# USB_CPLD.net
KiCad netlist of a schematic drawn in Altium Designer
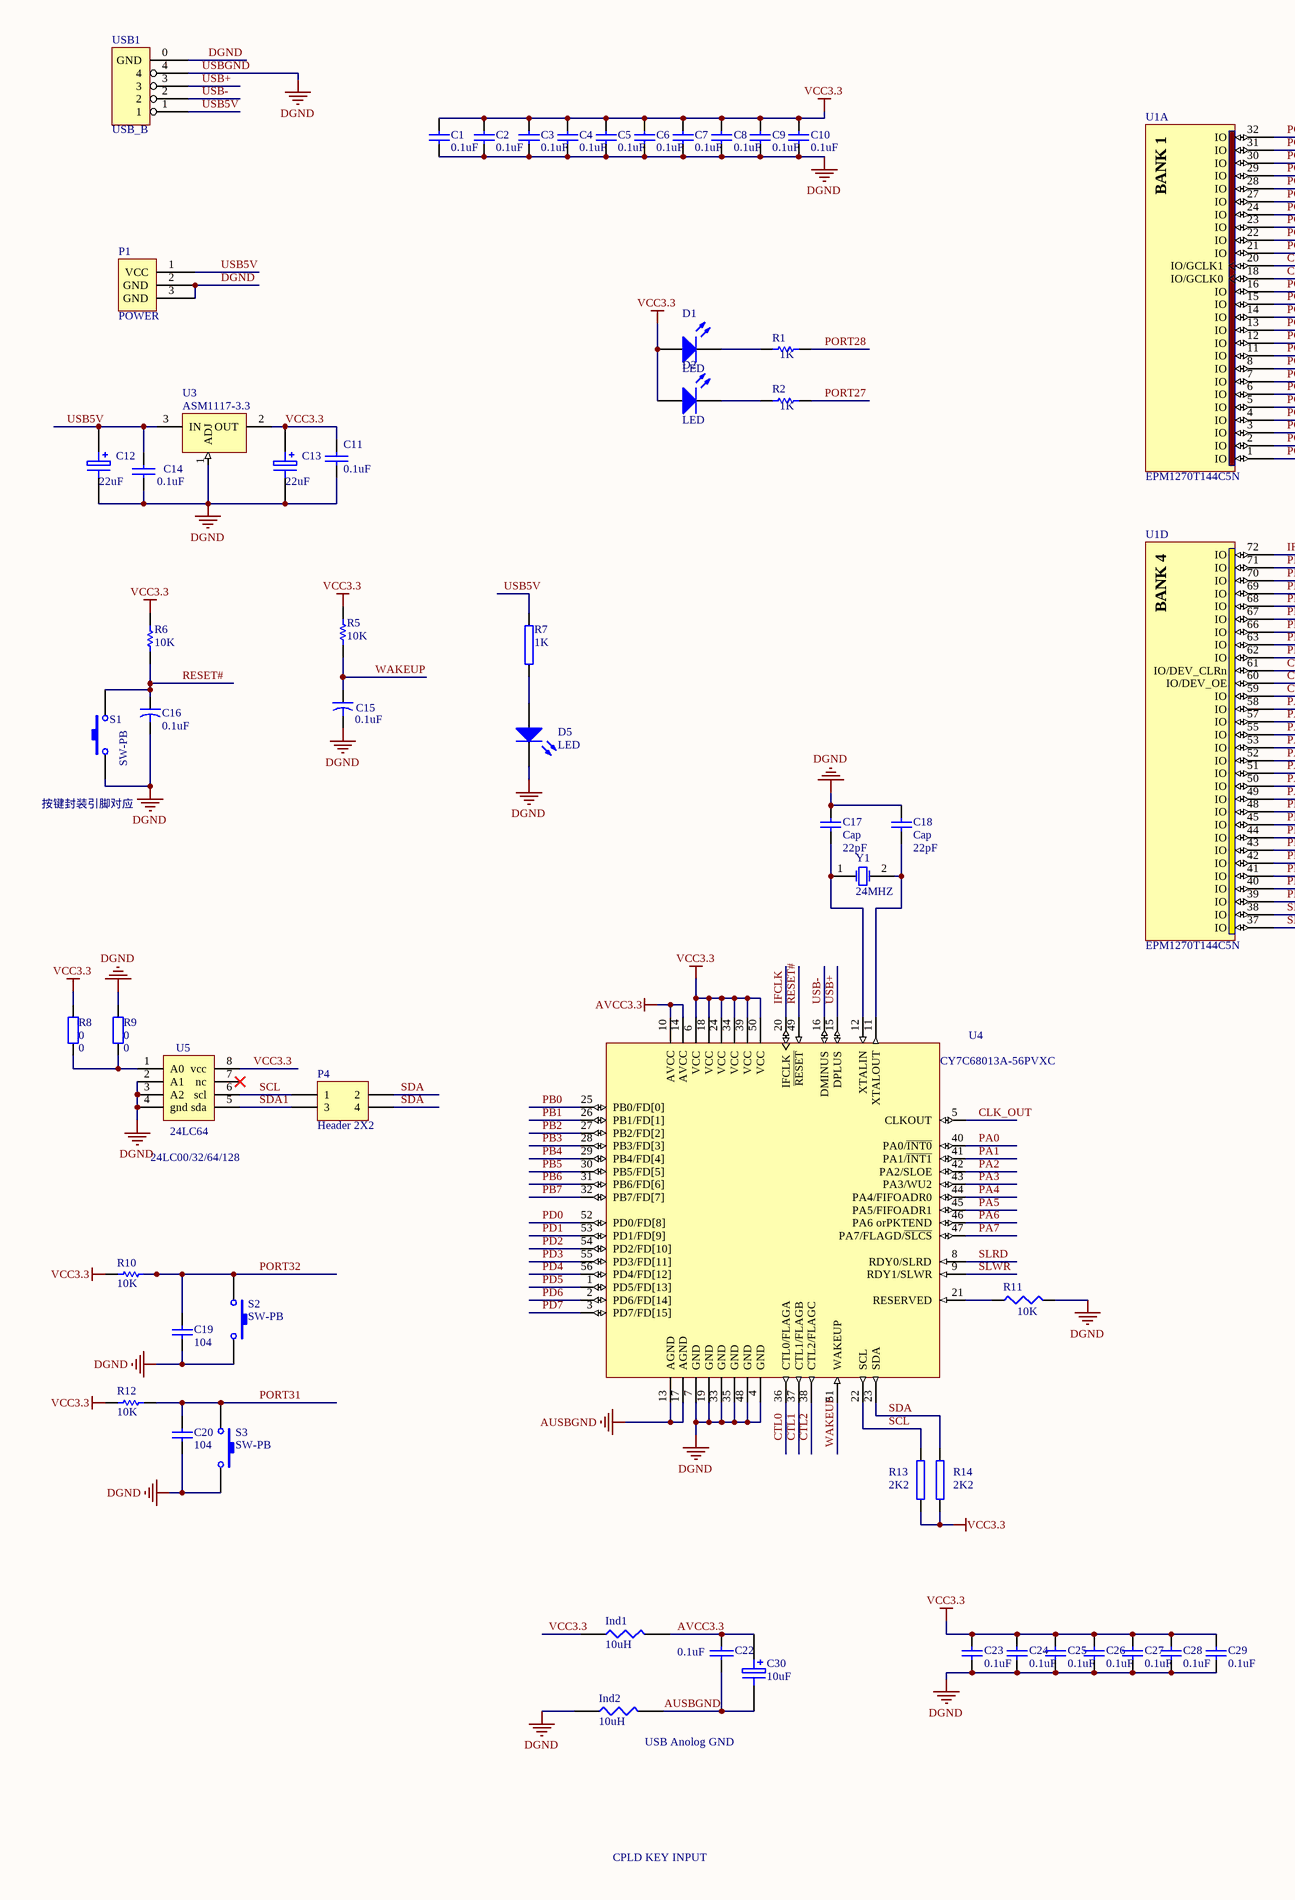
[diagram p0: USB_CPLD.SchDoc, left]
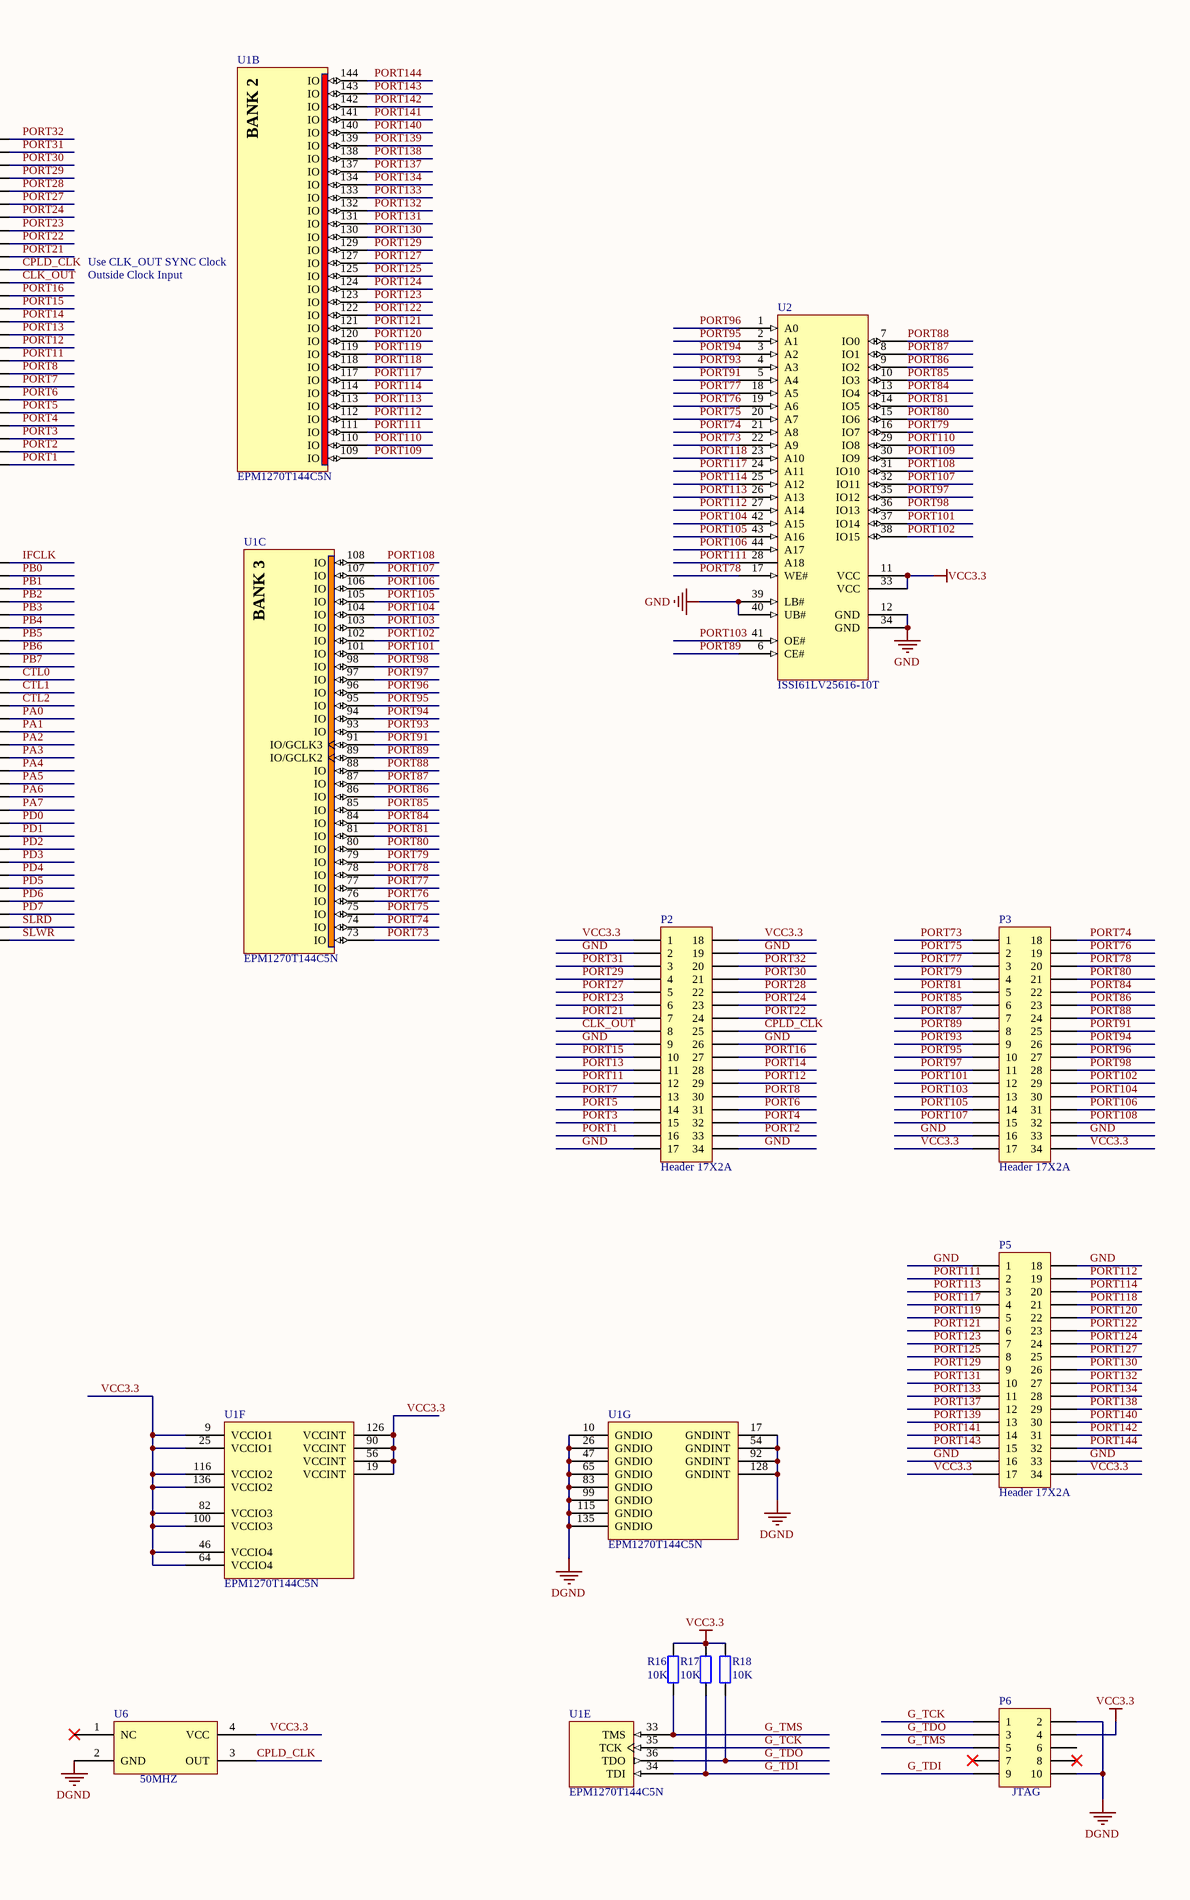
[diagram p1: USB_CPLD.SchDoc, right]

(export (version "E")
  (design (tool "Eeschema 10.0.6"))
  (components
    (comp (ref "C1")
      (value "0.1uF")
      (footprint "1608[0603]")
      (description "Capacitor (Semiconductor SIM Model)")
      (fields (field (name "PUBLISHER") "Altium Limited"))
      (libsource (lib "Miscellaneous Devices") (part "Cap Semi"))
    )
    (comp (ref "C2")
      (value "0.1uF")
      (footprint "1608[0603]")
      (description "Capacitor (Semiconductor SIM Model)")
      (fields (field (name "PUBLISHER") "Altium Limited"))
      (libsource (lib "Miscellaneous Devices") (part "Cap Semi"))
    )
    (comp (ref "C3")
      (value "0.1uF")
      (footprint "1608[0603]")
      (description "Capacitor (Semiconductor SIM Model)")
      (fields (field (name "Comment") "Cap Semi") (field (name "PUBLISHER") "Altium Limited"))
      (libsource (lib "Miscellaneous Devices") (part "Cap Semi"))
    )
    (comp (ref "C4")
      (value "0.1uF")
      (footprint "1608[0603]")
      (description "Capacitor (Semiconductor SIM Model)")
      (fields (field (name "Comment") "Cap Semi") (field (name "PUBLISHER") "Altium Limited"))
      (libsource (lib "Miscellaneous Devices") (part "Cap Semi"))
    )
    (comp (ref "C5")
      (value "0.1uF")
      (footprint "1608[0603]")
      (description "Capacitor (Semiconductor SIM Model)")
      (fields (field (name "Comment") "Cap Semi") (field (name "PUBLISHER") "Altium Limited"))
      (libsource (lib "Miscellaneous Devices") (part "Cap Semi"))
    )
    (comp (ref "C6")
      (value "0.1uF")
      (footprint "1608[0603]")
      (description "Capacitor (Semiconductor SIM Model)")
      (fields (field (name "Comment") "Cap Semi") (field (name "PUBLISHER") "Altium Limited"))
      (libsource (lib "Miscellaneous Devices") (part "Cap Semi"))
    )
    (comp (ref "C7")
      (value "0.1uF")
      (footprint "1608[0603]")
      (description "Capacitor (Semiconductor SIM Model)")
      (fields (field (name "Comment") "Cap Semi") (field (name "PUBLISHER") "Altium Limited"))
      (libsource (lib "Miscellaneous Devices") (part "Cap Semi"))
    )
    (comp (ref "C8")
      (value "0.1uF")
      (footprint "1608[0603]")
      (description "Capacitor (Semiconductor SIM Model)")
      (fields (field (name "Comment") "Cap Semi") (field (name "PUBLISHER") "Altium Limited"))
      (libsource (lib "Miscellaneous Devices") (part "Cap Semi"))
    )
    (comp (ref "C9")
      (value "0.1uF")
      (footprint "1608[0603]")
      (description "Capacitor (Semiconductor SIM Model)")
      (fields (field (name "Comment") "Cap Semi") (field (name "PUBLISHER") "Altium Limited"))
      (libsource (lib "Miscellaneous Devices") (part "Cap Semi"))
    )
    (comp (ref "C10")
      (value "0.1uF")
      (footprint "1608[0603]")
      (description "Capacitor (Semiconductor SIM Model)")
      (fields (field (name "Comment") "Cap Semi") (field (name "PUBLISHER") "Altium Limited"))
      (libsource (lib "Miscellaneous Devices") (part "Cap Semi"))
    )
    (comp (ref "C11")
      (value "0.1uF")
      (footprint "1608[0603]")
      (description "Capacitor")
      (libsource (lib "*") (part "CAP"))
    )
    (comp (ref "C12")
      (value "22uF")
      (footprint "3528")
      (description "Electrolytic Capacitor")
      (libsource (lib "*") (part "ELECTRO1"))
    )
    (comp (ref "C13")
      (value "22uF")
      (footprint "3528")
      (description "Electrolytic Capacitor")
      (libsource (lib "*") (part "ELECTRO1"))
    )
    (comp (ref "C14")
      (value "0.1uF")
      (footprint "1608[0603]")
      (description "Capacitor")
      (libsource (lib "*") (part "CAP"))
    )
    (comp (ref "C15")
      (value "0.1uF")
      (footprint "1206")
      (description "Capacitor")
      (fields (field (name "PUBLISHER") "Altium Limited"))
      (libsource (lib "*") (part "Cap2"))
    )
    (comp (ref "C16")
      (value "0.1uF")
      (footprint "1206")
      (description "Capacitor")
      (fields (field (name "PUBLISHER") "Altium Limited"))
      (libsource (lib "*") (part "Cap2"))
    )
    (comp (ref "C17")
      (value "Cap")
      (footprint "1608[0603]")
      (description "Capacitor")
      (fields (field (name "ALTIUM_VALUE") "22pF") (field (name "PUBLISHER") "Altium Limited"))
      (libsource (lib "*") (part "Cap"))
    )
    (comp (ref "C18")
      (value "Cap")
      (footprint "1608[0603]")
      (description "Capacitor")
      (fields (field (name "ALTIUM_VALUE") "22pF") (field (name "PUBLISHER") "Altium Limited"))
      (libsource (lib "*") (part "Cap"))
    )
    (comp (ref "C19")
      (value "104")
      (footprint "1608[0603]")
      (description "Capacitor (Semiconductor SIM Model)")
      (fields (field (name "PUBLISHER") "Altium Limited"))
      (libsource (lib "Miscellaneous Devices") (part "Cap Semi"))
    )
    (comp (ref "C20")
      (value "104")
      (footprint "1608[0603]")
      (description "Capacitor (Semiconductor SIM Model)")
      (fields (field (name "PUBLISHER") "Altium Limited"))
      (libsource (lib "Miscellaneous Devices") (part "Cap Semi"))
    )
    (comp (ref "C22")
      (value "0.1uF")
      (footprint "1608[0603]")
      (description "Capacitor")
      (libsource (lib "*") (part "CAP"))
    )
    (comp (ref "C23")
      (value "0.1uF")
      (footprint "1608[0603]")
      (description "Capacitor (Semiconductor SIM Model)")
      (fields (field (name "Comment") "Cap Semi") (field (name "PUBLISHER") "Altium Limited"))
      (libsource (lib "Miscellaneous Devices") (part "Cap Semi"))
    )
    (comp (ref "C24")
      (value "0.1uF")
      (footprint "1608[0603]")
      (description "Capacitor (Semiconductor SIM Model)")
      (fields (field (name "Comment") "Cap Semi") (field (name "PUBLISHER") "Altium Limited"))
      (libsource (lib "Miscellaneous Devices") (part "Cap Semi"))
    )
    (comp (ref "C25")
      (value "0.1uF")
      (footprint "1608[0603]")
      (description "Capacitor (Semiconductor SIM Model)")
      (fields (field (name "Comment") "Cap Semi") (field (name "PUBLISHER") "Altium Limited"))
      (libsource (lib "Miscellaneous Devices") (part "Cap Semi"))
    )
    (comp (ref "C26")
      (value "0.1uF")
      (footprint "1608[0603]")
      (description "Capacitor (Semiconductor SIM Model)")
      (fields (field (name "Comment") "Cap Semi") (field (name "PUBLISHER") "Altium Limited"))
      (libsource (lib "Miscellaneous Devices") (part "Cap Semi"))
    )
    (comp (ref "C27")
      (value "0.1uF")
      (footprint "1608[0603]")
      (description "Capacitor (Semiconductor SIM Model)")
      (fields (field (name "Comment") "Cap Semi") (field (name "PUBLISHER") "Altium Limited"))
      (libsource (lib "Miscellaneous Devices") (part "Cap Semi"))
    )
    (comp (ref "C28")
      (value "0.1uF")
      (footprint "1608[0603]")
      (description "Capacitor (Semiconductor SIM Model)")
      (fields (field (name "Comment") "Cap Semi") (field (name "PUBLISHER") "Altium Limited"))
      (libsource (lib "Miscellaneous Devices") (part "Cap Semi"))
    )
    (comp (ref "C29")
      (value "0.1uF")
      (footprint "1608[0603]")
      (description "Capacitor (Semiconductor SIM Model)")
      (fields (field (name "Comment") "Cap Semi") (field (name "PUBLISHER") "Altium Limited"))
      (libsource (lib "Miscellaneous Devices") (part "Cap Semi"))
    )
    (comp (ref "C30")
      (value "10uF")
      (footprint "1206")
      (description "Electrolytic Capacitor")
      (libsource (lib "*") (part "ELECTRO1"))
    )
    (comp (ref "D1")
      (value "LED")
      (footprint "LED-3")
      (description "Typical BLUE SiC LED")
      (fields (field (name "PUBLISHER") "Altium Limited"))
      (libsource (lib "*") (part "LED3"))
    )
    (comp (ref "D2")
      (value "LED")
      (footprint "LED-3")
      (description "Typical BLUE SiC LED")
      (fields (field (name "PUBLISHER") "Altium Limited"))
      (libsource (lib "*") (part "LED3"))
    )
    (comp (ref "D5")
      (value "LED")
      (footprint "LED-3")
      (description "Typical BLUE SiC LED")
      (fields (field (name "PUBLISHER") "Altium Limited"))
      (libsource (lib "*") (part "LED3"))
    )
    (comp (ref "Ind1") (value "10uH") (footprint "0805") (libsource (lib "*") (part "RES1")))
    (comp (ref "Ind2") (value "10uH") (footprint "0805") (libsource (lib "*") (part "RES1")))
    (comp (ref "P1") (value "POWER") (footprint "POWER_BIG") (libsource (lib "EP2C5T114核心板一") (part "POWER")))
    (comp (ref "P2")
      (value "Header 17X2A")
      (footprint "HDR2X17_CEN")
      (description "Header, 17-Pin, Dual row")
      (fields (field (name "PUBLISHER") "Altium Limited"))
      (libsource (lib "Miscellaneous Connectors") (part "Header 17X2A"))
    )
    (comp (ref "P3")
      (value "Header 17X2A")
      (footprint "HDR2X17_CEN")
      (description "Header, 17-Pin, Dual row")
      (fields (field (name "PUBLISHER") "Altium Limited"))
      (libsource (lib "Miscellaneous Connectors") (part "Header 17X2A"))
    )
    (comp (ref "P4")
      (value "Header 2X2")
      (footprint "HDR2X2")
      (description "Header, 2-Pin, Dual row")
      (fields (field (name "PUBLISHER") "Altium Limited"))
      (libsource (lib "Miscellaneous Connectors") (part "Header 2X2"))
    )
    (comp (ref "P5")
      (value "Header 17X2A")
      (footprint "HDR2X17_CEN")
      (description "Header, 17-Pin, Dual row")
      (fields (field (name "PUBLISHER") "Altium Limited"))
      (libsource (lib "Miscellaneous Connectors") (part "Header 17X2A"))
    )
    (comp (ref "P6")
      (value "JTAG")
      (footprint "HDR2X5")
      (description "Header, 5-Pin, Dual row")
      (fields (field (name "PUBLISHER") "Altium Limited"))
      (libsource (lib "*") (part "Header 5X2"))
    )
    (comp (ref "R1")
      (value "1K")
      (footprint "1608[0603]")
      (description "Resistor")
      (fields (field (name "Comment") "Res1") (field (name "PUBLISHER") "Altium Limited"))
      (libsource (lib "*") (part "Res1"))
    )
    (comp (ref "R2")
      (value "1K")
      (footprint "1608[0603]")
      (description "Resistor")
      (fields (field (name "Comment") "Res1") (field (name "PUBLISHER") "Altium Limited"))
      (libsource (lib "*") (part "Res1"))
    )
    (comp (ref "R5")
      (value "10K")
      (footprint "1608[0603]")
      (description "Resistor")
      (fields (field (name "PUBLISHER") "Altium Limited"))
      (libsource (lib "*") (part "Res1"))
    )
    (comp (ref "R6")
      (value "10K")
      (footprint "1608[0603]")
      (description "Resistor")
      (fields (field (name "PUBLISHER") "Altium Limited"))
      (libsource (lib "*") (part "Res1"))
    )
    (comp (ref "R7") (value "1K") (footprint "2012[0805]") (libsource (lib "*") (part "RES2")))
    (comp (ref "R8")
      (value "0")
      (footprint "1608[0603]")
      (description "Resistor")
      (fields (field (name "ALTIUM_VALUE") "0") (field (name "PUBLISHER") "Altium Limited"))
      (libsource (lib "Miscellaneous Devices") (part "Res2"))
    )
    (comp (ref "R9")
      (value "0")
      (footprint "1608[0603]")
      (description "Resistor")
      (fields (field (name "ALTIUM_VALUE") "0") (field (name "PUBLISHER") "Altium Limited"))
      (libsource (lib "Miscellaneous Devices") (part "Res2"))
    )
    (comp (ref "R10")
      (value "10K")
      (footprint "1608[0603]")
      (description "Resistor")
      (fields (field (name "PUBLISHER") "Altium Limited"))
      (libsource (lib "*") (part "Res1"))
    )
    (comp (ref "R11")
      (value "10K")
      (footprint "1608[0603]")
      (description "Resistor")
      (fields (field (name "Comment") "Res3") (field (name "PUBLISHER") "Altium Limited"))
      (libsource (lib "Miscellaneous Devices") (part "Res3"))
    )
    (comp (ref "R12")
      (value "10K")
      (footprint "1608[0603]")
      (description "Resistor")
      (fields (field (name "PUBLISHER") "Altium Limited"))
      (libsource (lib "*") (part "Res1"))
    )
    (comp (ref "R13") (value "2K2") (footprint "1608[0603]") (libsource (lib "*") (part "RES2")))
    (comp (ref "R14") (value "2K2") (footprint "1608[0603]") (libsource (lib "*") (part "RES2")))
    (comp (ref "R16")
      (value "10K")
      (footprint "1608[0603]")
      (description "Resistor")
      (fields (field (name "Comment") "300") (field (name "PUBLISHER") "Altium Limited"))
      (libsource (lib "*") (part "Res2"))
    )
    (comp (ref "R17")
      (value "10K")
      (footprint "1608[0603]")
      (description "Resistor")
      (fields (field (name "Comment") "300") (field (name "PUBLISHER") "Altium Limited"))
      (libsource (lib "*") (part "Res2"))
    )
    (comp (ref "R18")
      (value "10K")
      (footprint "1608[0603]")
      (description "Resistor")
      (fields (field (name "Comment") "300") (field (name "PUBLISHER") "Altium Limited"))
      (libsource (lib "*") (part "Res2"))
    )
    (comp (ref "S1")
      (value "SW-PB")
      (footprint "SW-6-6")
      (description "Switch")
      (fields (field (name "PUBLISHER") "Altium Limited"))
      (libsource (lib "*") (part "SW-PB"))
    )
    (comp (ref "S2")
      (value "SW-PB")
      (footprint "SW-6-6")
      (description "Switch")
      (fields (field (name "PUBLISHER") "Altium Limited"))
      (libsource (lib "*") (part "SW-PB"))
    )
    (comp (ref "S3")
      (value "SW-PB")
      (footprint "SW-6-6")
      (description "Switch")
      (fields (field (name "PUBLISHER") "Altium Limited"))
      (libsource (lib "*") (part "SW-PB"))
    )
    (comp (ref "U1")
      (value "EPM1270T144C5N")
      (footprint "TQFP144_N")
      (fields (field (name "PUBLISHER") "Altium Limited"))
      (libsource (lib "Altera MAX II") (part "EPM1270T144C5N"))
    )
    (comp (ref "U2")
      (value "ISSI61LV25616-10T")
      (footprint "TSOPII44")
      (description "IS61LV25616-10T  10ns Speed")
      (libsource (lib "logicusb") (part "IS61LV25616-10T"))
    )
    (comp (ref "U3")
      (value "ASM1117-3.3")
      (footprint "SOT223")
      (description "Three-Terminal Adjustable Output Positive Voltage Regulator")
      (libsource (lib "*") (part "LM317MAT(3)"))
    )
    (comp (ref "U4")
      (value "CY7C68013A-56PVXC")
      (footprint "O56")
      (fields (field (name "PUBLISHER") "Altium Limited"))
      (libsource (lib "Cypress USB High-Speed") (part "CY7C68013A-56PVXC"))
    )
    (comp (ref "U5") (value "24LC64") (footprint "SO-8") (libsource (lib "*") (part "24LC00")))
    (comp (ref "U6") (value "50MHZ") (footprint "OSC_50MHZ") (libsource (lib "XTAL") (part "OSC50MHZ")))
    (comp (ref "USB1") (value "USB_B") (footprint "USB-SQUARE") (libsource (lib "*") (part "USB_B")))
    (comp (ref "Y1")
      (value "24MHZ")
      (footprint "XTAL")
      (description "Crystal Oscillator")
      (fields (field (name "PUBLISHER") "Altium Limited"))
      (libsource (lib "*") (part "XTAL"))
    )
  )
  (nets
    (net (code "1") (name "/CLK_OUT") (class "Default")
      (node (ref "P2") (pin "8") (pinfunction "8_8") (pintype "passive"))
      (node (ref "U1") (pin "18") (pinfunction "IO/GCLK0_18") (pintype "bidirectional"))
      (node (ref "U4") (pin "5") (pinfunction "CLKOUT_5") (pintype "bidirectional"))
    )
    (net (code "2") (name "/CPLD_CLK") (class "Default")
      (node (ref "P2") (pin "25") (pinfunction "25_25") (pintype "passive"))
      (node (ref "U1") (pin "20") (pinfunction "IO/GCLK1_20") (pintype "bidirectional"))
      (node (ref "U6") (pin "3") (pinfunction "OUT_3") (pintype "passive"))
    )
    (net (code "3") (name "/CTL0") (class "Default")
      (node (ref "U1") (pin "61") (pinfunction "IO/DEV_CLRn_61") (pintype "bidirectional"))
      (node (ref "U4") (pin "36") (pinfunction "CTL0/FLAGA_36") (pintype "output"))
    )
    (net (code "4") (name "/CTL1") (class "Default")
      (node (ref "U1") (pin "60") (pinfunction "IO/DEV_OE_60") (pintype "bidirectional"))
      (node (ref "U4") (pin "37") (pinfunction "CTL1/FLAGB_37") (pintype "output"))
    )
    (net (code "5") (name "/CTL2") (class "Default")
      (node (ref "U1") (pin "59") (pinfunction "IO_59") (pintype "bidirectional"))
      (node (ref "U4") (pin "38") (pinfunction "CTL2/FLAGC_38") (pintype "output"))
    )
    (net (code "6") (name "/G_TCK") (class "Default")
      (node (ref "P6") (pin "1") (pinfunction "1_1") (pintype "passive"))
      (node (ref "U1") (pin "35") (pinfunction "TCK_35") (pintype "input"))
    )
    (net (code "7") (name "/G_TDI") (class "Default")
      (node (ref "P6") (pin "9") (pinfunction "9_9") (pintype "passive"))
      (node (ref "R17") (pin "1") (pinfunction "1_1") (pintype "passive"))
      (node (ref "U1") (pin "34") (pinfunction "TDI_34") (pintype "input"))
    )
    (net (code "8") (name "/G_TDO") (class "Default")
      (node (ref "P6") (pin "3") (pinfunction "3_3") (pintype "passive"))
      (node (ref "R18") (pin "1") (pinfunction "1_1") (pintype "passive"))
      (node (ref "U1") (pin "36") (pinfunction "TDO_36") (pintype "output"))
    )
    (net (code "9") (name "/G_TMS") (class "Default")
      (node (ref "P6") (pin "5") (pinfunction "5_5") (pintype "passive"))
      (node (ref "R16") (pin "1") (pinfunction "1_1") (pintype "passive"))
      (node (ref "U1") (pin "33") (pinfunction "TMS_33") (pintype "input"))
    )
    (net (code "10") (name "/IFCLK") (class "Default")
      (node (ref "U1") (pin "72") (pinfunction "IO_72") (pintype "bidirectional"))
      (node (ref "U4") (pin "20") (pinfunction "IFCLK_20") (pintype "bidirectional"))
    )
    (net (code "11") (name "/PA0") (class "Default")
      (node (ref "U1") (pin "58") (pinfunction "IO_58") (pintype "bidirectional"))
      (node (ref "U4") (pin "40") (pinfunction "PA0/~{INT0}_40") (pintype "bidirectional"))
    )
    (net (code "12") (name "/PA1") (class "Default")
      (node (ref "U1") (pin "57") (pinfunction "IO_57") (pintype "bidirectional"))
      (node (ref "U4") (pin "41") (pinfunction "PA1/~{INT1}_41") (pintype "bidirectional"))
    )
    (net (code "13") (name "/PA2") (class "Default")
      (node (ref "U1") (pin "55") (pinfunction "IO_55") (pintype "bidirectional"))
      (node (ref "U4") (pin "42") (pinfunction "PA2/SLOE_42") (pintype "bidirectional"))
    )
    (net (code "14") (name "/PA3") (class "Default")
      (node (ref "U1") (pin "53") (pinfunction "IO_53") (pintype "bidirectional"))
      (node (ref "U4") (pin "43") (pinfunction "PA3/WU2_43") (pintype "bidirectional"))
    )
    (net (code "15") (name "/PA4") (class "Default")
      (node (ref "U1") (pin "52") (pinfunction "IO_52") (pintype "bidirectional"))
      (node (ref "U4") (pin "44") (pinfunction "PA4/FIFOADR0_44") (pintype "bidirectional"))
    )
    (net (code "16") (name "/PA5") (class "Default")
      (node (ref "U1") (pin "51") (pinfunction "IO_51") (pintype "bidirectional"))
      (node (ref "U4") (pin "45") (pinfunction "PA5/FIFOADR1_45") (pintype "bidirectional"))
    )
    (net (code "17") (name "/PA6") (class "Default")
      (node (ref "U1") (pin "50") (pinfunction "IO_50") (pintype "bidirectional"))
      (node (ref "U4") (pin "46") (pinfunction "PA6_orPKTEND_46") (pintype "bidirectional"))
    )
    (net (code "18") (name "/PA7") (class "Default")
      (node (ref "U1") (pin "49") (pinfunction "IO_49") (pintype "bidirectional"))
      (node (ref "U4") (pin "47") (pinfunction "PA7/FLAGD/~{SLCS}_47") (pintype "bidirectional"))
    )
    (net (code "19") (name "/PB0") (class "Default")
      (node (ref "U1") (pin "71") (pinfunction "IO_71") (pintype "bidirectional"))
      (node (ref "U4") (pin "25") (pinfunction "PB0/FD[0]_25") (pintype "bidirectional"))
    )
    (net (code "20") (name "/PB1") (class "Default")
      (node (ref "U1") (pin "70") (pinfunction "IO_70") (pintype "bidirectional"))
      (node (ref "U4") (pin "26") (pinfunction "PB1/FD[1]_26") (pintype "bidirectional"))
    )
    (net (code "21") (name "/PB2") (class "Default")
      (node (ref "U1") (pin "69") (pinfunction "IO_69") (pintype "bidirectional"))
      (node (ref "U4") (pin "27") (pinfunction "PB2/FD[2]_27") (pintype "bidirectional"))
    )
    (net (code "22") (name "/PB3") (class "Default")
      (node (ref "U1") (pin "68") (pinfunction "IO_68") (pintype "bidirectional"))
      (node (ref "U4") (pin "28") (pinfunction "PB3/FD[3]_28") (pintype "bidirectional"))
    )
    (net (code "23") (name "/PB4") (class "Default")
      (node (ref "U1") (pin "67") (pinfunction "IO_67") (pintype "bidirectional"))
      (node (ref "U4") (pin "29") (pinfunction "PB4/FD[4]_29") (pintype "bidirectional"))
    )
    (net (code "24") (name "/PB5") (class "Default")
      (node (ref "U1") (pin "66") (pinfunction "IO_66") (pintype "bidirectional"))
      (node (ref "U4") (pin "30") (pinfunction "PB5/FD[5]_30") (pintype "bidirectional"))
    )
    (net (code "25") (name "/PB6") (class "Default")
      (node (ref "U1") (pin "63") (pinfunction "IO_63") (pintype "bidirectional"))
      (node (ref "U4") (pin "31") (pinfunction "PB6/FD[6]_31") (pintype "bidirectional"))
    )
    (net (code "26") (name "/PB7") (class "Default")
      (node (ref "U1") (pin "62") (pinfunction "IO_62") (pintype "bidirectional"))
      (node (ref "U4") (pin "32") (pinfunction "PB7/FD[7]_32") (pintype "bidirectional"))
    )
    (net (code "27") (name "/PD0") (class "Default")
      (node (ref "U1") (pin "48") (pinfunction "IO_48") (pintype "bidirectional"))
      (node (ref "U4") (pin "52") (pinfunction "PD0/FD[8]_52") (pintype "bidirectional"))
    )
    (net (code "28") (name "/PD1") (class "Default")
      (node (ref "U1") (pin "45") (pinfunction "IO_45") (pintype "bidirectional"))
      (node (ref "U4") (pin "53") (pinfunction "PD1/FD[9]_53") (pintype "bidirectional"))
    )
    (net (code "29") (name "/PD2") (class "Default")
      (node (ref "U1") (pin "44") (pinfunction "IO_44") (pintype "bidirectional"))
      (node (ref "U4") (pin "54") (pinfunction "PD2/FD[10]_54") (pintype "bidirectional"))
    )
    (net (code "30") (name "/PD3") (class "Default")
      (node (ref "U1") (pin "43") (pinfunction "IO_43") (pintype "bidirectional"))
      (node (ref "U4") (pin "55") (pinfunction "PD3/FD[11]_55") (pintype "bidirectional"))
    )
    (net (code "31") (name "/PD4") (class "Default")
      (node (ref "U1") (pin "42") (pinfunction "IO_42") (pintype "bidirectional"))
      (node (ref "U4") (pin "56") (pinfunction "PD4/FD[12]_56") (pintype "bidirectional"))
    )
    (net (code "32") (name "/PD5") (class "Default")
      (node (ref "U1") (pin "41") (pinfunction "IO_41") (pintype "bidirectional"))
      (node (ref "U4") (pin "1") (pinfunction "PD5/FD[13]_1") (pintype "bidirectional"))
    )
    (net (code "33") (name "/PD6") (class "Default")
      (node (ref "U1") (pin "40") (pinfunction "IO_40") (pintype "bidirectional"))
      (node (ref "U4") (pin "2") (pinfunction "PD6/FD[14]_2") (pintype "bidirectional"))
    )
    (net (code "34") (name "/PD7") (class "Default")
      (node (ref "U1") (pin "39") (pinfunction "IO_39") (pintype "bidirectional"))
      (node (ref "U4") (pin "3") (pinfunction "PD7/FD[15]_3") (pintype "bidirectional"))
    )
    (net (code "35") (name "/PORT1") (class "Default")
      (node (ref "P2") (pin "16") (pinfunction "16_16") (pintype "passive"))
      (node (ref "U1") (pin "1") (pinfunction "IO_1") (pintype "bidirectional"))
    )
    (net (code "36") (name "/PORT2") (class "Default")
      (node (ref "P2") (pin "33") (pinfunction "33_33") (pintype "passive"))
      (node (ref "U1") (pin "2") (pinfunction "IO_2") (pintype "bidirectional"))
    )
    (net (code "37") (name "/PORT3") (class "Default")
      (node (ref "P2") (pin "15") (pinfunction "15_15") (pintype "passive"))
      (node (ref "U1") (pin "3") (pinfunction "IO_3") (pintype "bidirectional"))
    )
    (net (code "38") (name "/PORT4") (class "Default")
      (node (ref "P2") (pin "32") (pinfunction "32_32") (pintype "passive"))
      (node (ref "U1") (pin "4") (pinfunction "IO_4") (pintype "bidirectional"))
    )
    (net (code "39") (name "/PORT5") (class "Default")
      (node (ref "P2") (pin "14") (pinfunction "14_14") (pintype "passive"))
      (node (ref "U1") (pin "5") (pinfunction "IO_5") (pintype "bidirectional"))
    )
    (net (code "40") (name "/PORT6") (class "Default")
      (node (ref "P2") (pin "31") (pinfunction "31_31") (pintype "passive"))
      (node (ref "U1") (pin "6") (pinfunction "IO_6") (pintype "bidirectional"))
    )
    (net (code "41") (name "/PORT7") (class "Default")
      (node (ref "P2") (pin "13") (pinfunction "13_13") (pintype "passive"))
      (node (ref "U1") (pin "7") (pinfunction "IO_7") (pintype "bidirectional"))
    )
    (net (code "42") (name "/PORT8") (class "Default")
      (node (ref "P2") (pin "30") (pinfunction "30_30") (pintype "passive"))
      (node (ref "U1") (pin "8") (pinfunction "IO_8") (pintype "bidirectional"))
    )
    (net (code "43") (name "/PORT11") (class "Default")
      (node (ref "P2") (pin "12") (pinfunction "12_12") (pintype "passive"))
      (node (ref "U1") (pin "11") (pinfunction "IO_11") (pintype "bidirectional"))
    )
    (net (code "44") (name "/PORT12") (class "Default")
      (node (ref "P2") (pin "29") (pinfunction "29_29") (pintype "passive"))
      (node (ref "U1") (pin "12") (pinfunction "IO_12") (pintype "bidirectional"))
    )
    (net (code "45") (name "/PORT13") (class "Default")
      (node (ref "P2") (pin "11") (pinfunction "11_11") (pintype "passive"))
      (node (ref "U1") (pin "13") (pinfunction "IO_13") (pintype "bidirectional"))
    )
    (net (code "46") (name "/PORT14") (class "Default")
      (node (ref "P2") (pin "28") (pinfunction "28_28") (pintype "passive"))
      (node (ref "U1") (pin "14") (pinfunction "IO_14") (pintype "bidirectional"))
    )
    (net (code "47") (name "/PORT15") (class "Default")
      (node (ref "P2") (pin "10") (pinfunction "10_10") (pintype "passive"))
      (node (ref "U1") (pin "15") (pinfunction "IO_15") (pintype "bidirectional"))
    )
    (net (code "48") (name "/PORT16") (class "Default")
      (node (ref "P2") (pin "27") (pinfunction "27_27") (pintype "passive"))
      (node (ref "U1") (pin "16") (pinfunction "IO_16") (pintype "bidirectional"))
    )
    (net (code "49") (name "/PORT21") (class "Default")
      (node (ref "P2") (pin "7") (pinfunction "7_7") (pintype "passive"))
      (node (ref "U1") (pin "21") (pinfunction "IO_21") (pintype "bidirectional"))
    )
    (net (code "50") (name "/PORT22") (class "Default")
      (node (ref "P2") (pin "24") (pinfunction "24_24") (pintype "passive"))
      (node (ref "U1") (pin "22") (pinfunction "IO_22") (pintype "bidirectional"))
    )
    (net (code "51") (name "/PORT23") (class "Default")
      (node (ref "P2") (pin "6") (pinfunction "6_6") (pintype "passive"))
      (node (ref "U1") (pin "23") (pinfunction "IO_23") (pintype "bidirectional"))
    )
    (net (code "52") (name "/PORT24") (class "Default")
      (node (ref "P2") (pin "23") (pinfunction "23_23") (pintype "passive"))
      (node (ref "U1") (pin "24") (pinfunction "IO_24") (pintype "bidirectional"))
    )
    (net (code "53") (name "/PORT27") (class "Default")
      (node (ref "P2") (pin "5") (pinfunction "5_5") (pintype "passive"))
      (node (ref "R2") (pin "2") (pinfunction "2_2") (pintype "passive"))
      (node (ref "U1") (pin "27") (pinfunction "IO_27") (pintype "bidirectional"))
    )
    (net (code "54") (name "/PORT28") (class "Default")
      (node (ref "P2") (pin "22") (pinfunction "22_22") (pintype "passive"))
      (node (ref "R1") (pin "2") (pinfunction "2_2") (pintype "passive"))
      (node (ref "U1") (pin "28") (pinfunction "IO_28") (pintype "bidirectional"))
    )
    (net (code "55") (name "/PORT29") (class "Default")
      (node (ref "P2") (pin "4") (pinfunction "4_4") (pintype "passive"))
      (node (ref "U1") (pin "29") (pinfunction "IO_29") (pintype "bidirectional"))
    )
    (net (code "56") (name "/PORT30") (class "Default")
      (node (ref "P2") (pin "21") (pinfunction "21_21") (pintype "passive"))
      (node (ref "U1") (pin "30") (pinfunction "IO_30") (pintype "bidirectional"))
    )
    (net (code "57") (name "/PORT31") (class "Default")
      (node (ref "C20") (pin "1") (pinfunction "1_1") (pintype "passive"))
      (node (ref "P2") (pin "3") (pinfunction "3_3") (pintype "passive"))
      (node (ref "R12") (pin "1") (pinfunction "1_1") (pintype "passive"))
      (node (ref "S3") (pin "1") (pinfunction "1_1") (pintype "passive"))
      (node (ref "U1") (pin "31") (pinfunction "IO_31") (pintype "bidirectional"))
    )
    (net (code "58") (name "/PORT32") (class "Default")
      (node (ref "C19") (pin "1") (pinfunction "1_1") (pintype "passive"))
      (node (ref "P2") (pin "20") (pinfunction "20_20") (pintype "passive"))
      (node (ref "R10") (pin "1") (pinfunction "1_1") (pintype "passive"))
      (node (ref "S2") (pin "1") (pinfunction "1_1") (pintype "passive"))
      (node (ref "U1") (pin "32") (pinfunction "IO_32") (pintype "bidirectional"))
    )
    (net (code "59") (name "/PORT73") (class "Default")
      (node (ref "P3") (pin "1") (pinfunction "1_1") (pintype "passive"))
      (node (ref "U1") (pin "73") (pinfunction "IO_73") (pintype "bidirectional"))
      (node (ref "U2") (pin "22") (pinfunction "A9_22") (pintype "input"))
    )
    (net (code "60") (name "/PORT74") (class "Default")
      (node (ref "P3") (pin "18") (pinfunction "18_18") (pintype "passive"))
      (node (ref "U1") (pin "74") (pinfunction "IO_74") (pintype "bidirectional"))
      (node (ref "U2") (pin "21") (pinfunction "A8_21") (pintype "input"))
    )
    (net (code "61") (name "/PORT75") (class "Default")
      (node (ref "P3") (pin "2") (pinfunction "2_2") (pintype "passive"))
      (node (ref "U1") (pin "75") (pinfunction "IO_75") (pintype "bidirectional"))
      (node (ref "U2") (pin "20") (pinfunction "A7_20") (pintype "input"))
    )
    (net (code "62") (name "/PORT76") (class "Default")
      (node (ref "P3") (pin "19") (pinfunction "19_19") (pintype "passive"))
      (node (ref "U1") (pin "76") (pinfunction "IO_76") (pintype "bidirectional"))
      (node (ref "U2") (pin "19") (pinfunction "A6_19") (pintype "input"))
    )
    (net (code "63") (name "/PORT77") (class "Default")
      (node (ref "P3") (pin "3") (pinfunction "3_3") (pintype "passive"))
      (node (ref "U1") (pin "77") (pinfunction "IO_77") (pintype "bidirectional"))
      (node (ref "U2") (pin "18") (pinfunction "A5_18") (pintype "input"))
    )
    (net (code "64") (name "/PORT78") (class "Default")
      (node (ref "P3") (pin "20") (pinfunction "20_20") (pintype "passive"))
      (node (ref "U1") (pin "78") (pinfunction "IO_78") (pintype "bidirectional"))
      (node (ref "U2") (pin "17") (pinfunction "WE#_17") (pintype "input"))
    )
    (net (code "65") (name "/PORT79") (class "Default")
      (node (ref "P3") (pin "4") (pinfunction "4_4") (pintype "passive"))
      (node (ref "U1") (pin "79") (pinfunction "IO_79") (pintype "bidirectional"))
      (node (ref "U2") (pin "16") (pinfunction "IO7_16") (pintype "bidirectional"))
    )
    (net (code "66") (name "/PORT80") (class "Default")
      (node (ref "P3") (pin "21") (pinfunction "21_21") (pintype "passive"))
      (node (ref "U1") (pin "80") (pinfunction "IO_80") (pintype "bidirectional"))
      (node (ref "U2") (pin "15") (pinfunction "IO6_15") (pintype "bidirectional"))
    )
    (net (code "67") (name "/PORT81") (class "Default")
      (node (ref "P3") (pin "5") (pinfunction "5_5") (pintype "passive"))
      (node (ref "U1") (pin "81") (pinfunction "IO_81") (pintype "bidirectional"))
      (node (ref "U2") (pin "14") (pinfunction "IO5_14") (pintype "bidirectional"))
    )
    (net (code "68") (name "/PORT84") (class "Default")
      (node (ref "P3") (pin "22") (pinfunction "22_22") (pintype "passive"))
      (node (ref "U1") (pin "84") (pinfunction "IO_84") (pintype "bidirectional"))
      (node (ref "U2") (pin "13") (pinfunction "IO4_13") (pintype "bidirectional"))
    )
    (net (code "69") (name "/PORT85") (class "Default")
      (node (ref "P3") (pin "6") (pinfunction "6_6") (pintype "passive"))
      (node (ref "U1") (pin "85") (pinfunction "IO_85") (pintype "bidirectional"))
      (node (ref "U2") (pin "10") (pinfunction "IO3_10") (pintype "bidirectional"))
    )
    (net (code "70") (name "/PORT86") (class "Default")
      (node (ref "P3") (pin "23") (pinfunction "23_23") (pintype "passive"))
      (node (ref "U1") (pin "86") (pinfunction "IO_86") (pintype "bidirectional"))
      (node (ref "U2") (pin "9") (pinfunction "IO2_9") (pintype "bidirectional"))
    )
    (net (code "71") (name "/PORT87") (class "Default")
      (node (ref "P3") (pin "7") (pinfunction "7_7") (pintype "passive"))
      (node (ref "U1") (pin "87") (pinfunction "IO_87") (pintype "bidirectional"))
      (node (ref "U2") (pin "8") (pinfunction "IO1_8") (pintype "bidirectional"))
    )
    (net (code "72") (name "/PORT88") (class "Default")
      (node (ref "P3") (pin "24") (pinfunction "24_24") (pintype "passive"))
      (node (ref "U1") (pin "88") (pinfunction "IO_88") (pintype "bidirectional"))
      (node (ref "U2") (pin "7") (pinfunction "IO0_7") (pintype "bidirectional"))
    )
    (net (code "73") (name "/PORT89") (class "Default")
      (node (ref "P3") (pin "8") (pinfunction "8_8") (pintype "passive"))
      (node (ref "U1") (pin "89") (pinfunction "IO/GCLK2_89") (pintype "bidirectional"))
      (node (ref "U2") (pin "6") (pinfunction "CE#_6") (pintype "input"))
    )
    (net (code "74") (name "/PORT91") (class "Default")
      (node (ref "P3") (pin "25") (pinfunction "25_25") (pintype "passive"))
      (node (ref "U1") (pin "91") (pinfunction "IO/GCLK3_91") (pintype "bidirectional"))
      (node (ref "U2") (pin "5") (pinfunction "A4_5") (pintype "input"))
    )
    (net (code "75") (name "/PORT93") (class "Default")
      (node (ref "P3") (pin "9") (pinfunction "9_9") (pintype "passive"))
      (node (ref "U1") (pin "93") (pinfunction "IO_93") (pintype "bidirectional"))
      (node (ref "U2") (pin "4") (pinfunction "A3_4") (pintype "input"))
    )
    (net (code "76") (name "/PORT94") (class "Default")
      (node (ref "P3") (pin "26") (pinfunction "26_26") (pintype "passive"))
      (node (ref "U1") (pin "94") (pinfunction "IO_94") (pintype "bidirectional"))
      (node (ref "U2") (pin "3") (pinfunction "A2_3") (pintype "input"))
    )
    (net (code "77") (name "/PORT95") (class "Default")
      (node (ref "P3") (pin "10") (pinfunction "10_10") (pintype "passive"))
      (node (ref "U1") (pin "95") (pinfunction "IO_95") (pintype "bidirectional"))
      (node (ref "U2") (pin "2") (pinfunction "A1_2") (pintype "input"))
    )
    (net (code "78") (name "/PORT96") (class "Default")
      (node (ref "P3") (pin "27") (pinfunction "27_27") (pintype "passive"))
      (node (ref "U1") (pin "96") (pinfunction "IO_96") (pintype "bidirectional"))
      (node (ref "U2") (pin "1") (pinfunction "A0_1") (pintype "input"))
    )
    (net (code "79") (name "/PORT97") (class "Default")
      (node (ref "P3") (pin "11") (pinfunction "11_11") (pintype "passive"))
      (node (ref "U1") (pin "97") (pinfunction "IO_97") (pintype "bidirectional"))
      (node (ref "U2") (pin "35") (pinfunction "IO12_35") (pintype "bidirectional"))
    )
    (net (code "80") (name "/PORT98") (class "Default")
      (node (ref "P3") (pin "28") (pinfunction "28_28") (pintype "passive"))
      (node (ref "U1") (pin "98") (pinfunction "IO_98") (pintype "bidirectional"))
      (node (ref "U2") (pin "36") (pinfunction "IO13_36") (pintype "bidirectional"))
    )
    (net (code "81") (name "/PORT101") (class "Default")
      (node (ref "P3") (pin "12") (pinfunction "12_12") (pintype "passive"))
      (node (ref "U1") (pin "101") (pinfunction "IO_101") (pintype "bidirectional"))
      (node (ref "U2") (pin "37") (pinfunction "IO14_37") (pintype "bidirectional"))
    )
    (net (code "82") (name "/PORT102") (class "Default")
      (node (ref "P3") (pin "29") (pinfunction "29_29") (pintype "passive"))
      (node (ref "U1") (pin "102") (pinfunction "IO_102") (pintype "bidirectional"))
      (node (ref "U2") (pin "38") (pinfunction "IO15_38") (pintype "bidirectional"))
    )
    (net (code "83") (name "/PORT103") (class "Default")
      (node (ref "P3") (pin "13") (pinfunction "13_13") (pintype "passive"))
      (node (ref "U1") (pin "103") (pinfunction "IO_103") (pintype "bidirectional"))
      (node (ref "U2") (pin "41") (pinfunction "OE#_41") (pintype "input"))
    )
    (net (code "84") (name "/PORT104") (class "Default")
      (node (ref "P3") (pin "30") (pinfunction "30_30") (pintype "passive"))
      (node (ref "U1") (pin "104") (pinfunction "IO_104") (pintype "bidirectional"))
      (node (ref "U2") (pin "42") (pinfunction "A15_42") (pintype "input"))
    )
    (net (code "85") (name "/PORT105") (class "Default")
      (node (ref "P3") (pin "14") (pinfunction "14_14") (pintype "passive"))
      (node (ref "U1") (pin "105") (pinfunction "IO_105") (pintype "bidirectional"))
      (node (ref "U2") (pin "43") (pinfunction "A16_43") (pintype "input"))
    )
    (net (code "86") (name "/PORT106") (class "Default")
      (node (ref "P3") (pin "31") (pinfunction "31_31") (pintype "passive"))
      (node (ref "U1") (pin "106") (pinfunction "IO_106") (pintype "bidirectional"))
      (node (ref "U2") (pin "44") (pinfunction "A17_44") (pintype "input"))
    )
    (net (code "87") (name "/PORT107") (class "Default")
      (node (ref "P3") (pin "15") (pinfunction "15_15") (pintype "passive"))
      (node (ref "U1") (pin "107") (pinfunction "IO_107") (pintype "bidirectional"))
      (node (ref "U2") (pin "32") (pinfunction "IO11_32") (pintype "bidirectional"))
    )
    (net (code "88") (name "/PORT108") (class "Default")
      (node (ref "P3") (pin "32") (pinfunction "32_32") (pintype "passive"))
      (node (ref "U1") (pin "108") (pinfunction "IO_108") (pintype "bidirectional"))
      (node (ref "U2") (pin "31") (pinfunction "IO10_31") (pintype "bidirectional"))
    )
    (net (code "89") (name "/PORT109") (class "Default")
      (node (ref "U1") (pin "109") (pinfunction "IO_109") (pintype "bidirectional"))
      (node (ref "U2") (pin "30") (pinfunction "IO9_30") (pintype "bidirectional"))
    )
    (net (code "90") (name "/PORT110") (class "Default")
      (node (ref "U1") (pin "110") (pinfunction "IO_110") (pintype "bidirectional"))
      (node (ref "U2") (pin "29") (pinfunction "IO8_29") (pintype "bidirectional"))
    )
    (net (code "91") (name "/PORT111") (class "Default")
      (node (ref "P5") (pin "2") (pinfunction "2_2") (pintype "passive"))
      (node (ref "U1") (pin "111") (pinfunction "IO_111") (pintype "bidirectional"))
      (node (ref "U2") (pin "28") (pinfunction "A18_28") (pintype "open_collector"))
    )
    (net (code "92") (name "/PORT112") (class "Default")
      (node (ref "P5") (pin "19") (pinfunction "19_19") (pintype "passive"))
      (node (ref "U1") (pin "112") (pinfunction "IO_112") (pintype "bidirectional"))
      (node (ref "U2") (pin "27") (pinfunction "A14_27") (pintype "input"))
    )
    (net (code "93") (name "/PORT113") (class "Default")
      (node (ref "P5") (pin "3") (pinfunction "3_3") (pintype "passive"))
      (node (ref "U1") (pin "113") (pinfunction "IO_113") (pintype "bidirectional"))
      (node (ref "U2") (pin "26") (pinfunction "A13_26") (pintype "input"))
    )
    (net (code "94") (name "/PORT114") (class "Default")
      (node (ref "P5") (pin "20") (pinfunction "20_20") (pintype "passive"))
      (node (ref "U1") (pin "114") (pinfunction "IO_114") (pintype "bidirectional"))
      (node (ref "U2") (pin "25") (pinfunction "A12_25") (pintype "input"))
    )
    (net (code "95") (name "/PORT117") (class "Default")
      (node (ref "P5") (pin "4") (pinfunction "4_4") (pintype "passive"))
      (node (ref "U1") (pin "117") (pinfunction "IO_117") (pintype "bidirectional"))
      (node (ref "U2") (pin "24") (pinfunction "A11_24") (pintype "input"))
    )
    (net (code "96") (name "/PORT118") (class "Default")
      (node (ref "P5") (pin "21") (pinfunction "21_21") (pintype "passive"))
      (node (ref "U1") (pin "118") (pinfunction "IO_118") (pintype "bidirectional"))
      (node (ref "U2") (pin "23") (pinfunction "A10_23") (pintype "input"))
    )
    (net (code "97") (name "/PORT119") (class "Default")
      (node (ref "P5") (pin "5") (pinfunction "5_5") (pintype "passive"))
      (node (ref "U1") (pin "119") (pinfunction "IO_119") (pintype "bidirectional"))
    )
    (net (code "98") (name "/PORT120") (class "Default")
      (node (ref "P5") (pin "22") (pinfunction "22_22") (pintype "passive"))
      (node (ref "U1") (pin "120") (pinfunction "IO_120") (pintype "bidirectional"))
    )
    (net (code "99") (name "/PORT121") (class "Default")
      (node (ref "P5") (pin "6") (pinfunction "6_6") (pintype "passive"))
      (node (ref "U1") (pin "121") (pinfunction "IO_121") (pintype "bidirectional"))
    )
    (net (code "100") (name "/PORT122") (class "Default")
      (node (ref "P5") (pin "23") (pinfunction "23_23") (pintype "passive"))
      (node (ref "U1") (pin "122") (pinfunction "IO_122") (pintype "bidirectional"))
    )
    (net (code "101") (name "/PORT123") (class "Default")
      (node (ref "P5") (pin "7") (pinfunction "7_7") (pintype "passive"))
      (node (ref "U1") (pin "123") (pinfunction "IO_123") (pintype "bidirectional"))
    )
    (net (code "102") (name "/PORT124") (class "Default")
      (node (ref "P5") (pin "24") (pinfunction "24_24") (pintype "passive"))
      (node (ref "U1") (pin "124") (pinfunction "IO_124") (pintype "bidirectional"))
    )
    (net (code "103") (name "/PORT125") (class "Default")
      (node (ref "P5") (pin "8") (pinfunction "8_8") (pintype "passive"))
      (node (ref "U1") (pin "125") (pinfunction "IO_125") (pintype "bidirectional"))
    )
    (net (code "104") (name "/PORT127") (class "Default")
      (node (ref "P5") (pin "25") (pinfunction "25_25") (pintype "passive"))
      (node (ref "U1") (pin "127") (pinfunction "IO_127") (pintype "bidirectional"))
    )
    (net (code "105") (name "/PORT129") (class "Default")
      (node (ref "P5") (pin "9") (pinfunction "9_9") (pintype "passive"))
      (node (ref "U1") (pin "129") (pinfunction "IO_129") (pintype "bidirectional"))
    )
    (net (code "106") (name "/PORT130") (class "Default")
      (node (ref "P5") (pin "26") (pinfunction "26_26") (pintype "passive"))
      (node (ref "U1") (pin "130") (pinfunction "IO_130") (pintype "bidirectional"))
    )
    (net (code "107") (name "/PORT131") (class "Default")
      (node (ref "P5") (pin "10") (pinfunction "10_10") (pintype "passive"))
      (node (ref "U1") (pin "131") (pinfunction "IO_131") (pintype "bidirectional"))
    )
    (net (code "108") (name "/PORT132") (class "Default")
      (node (ref "P5") (pin "27") (pinfunction "27_27") (pintype "passive"))
      (node (ref "U1") (pin "132") (pinfunction "IO_132") (pintype "bidirectional"))
    )
    (net (code "109") (name "/PORT133") (class "Default")
      (node (ref "P5") (pin "11") (pinfunction "11_11") (pintype "passive"))
      (node (ref "U1") (pin "133") (pinfunction "IO_133") (pintype "bidirectional"))
    )
    (net (code "110") (name "/PORT134") (class "Default")
      (node (ref "P5") (pin "28") (pinfunction "28_28") (pintype "passive"))
      (node (ref "U1") (pin "134") (pinfunction "IO_134") (pintype "bidirectional"))
    )
    (net (code "111") (name "/PORT137") (class "Default")
      (node (ref "P5") (pin "12") (pinfunction "12_12") (pintype "passive"))
      (node (ref "U1") (pin "137") (pinfunction "IO_137") (pintype "bidirectional"))
    )
    (net (code "112") (name "/PORT138") (class "Default")
      (node (ref "P5") (pin "29") (pinfunction "29_29") (pintype "passive"))
      (node (ref "U1") (pin "138") (pinfunction "IO_138") (pintype "bidirectional"))
    )
    (net (code "113") (name "/PORT139") (class "Default")
      (node (ref "P5") (pin "13") (pinfunction "13_13") (pintype "passive"))
      (node (ref "U1") (pin "139") (pinfunction "IO_139") (pintype "bidirectional"))
    )
    (net (code "114") (name "/PORT140") (class "Default")
      (node (ref "P5") (pin "30") (pinfunction "30_30") (pintype "passive"))
      (node (ref "U1") (pin "140") (pinfunction "IO_140") (pintype "bidirectional"))
    )
    (net (code "115") (name "/PORT141") (class "Default")
      (node (ref "P5") (pin "14") (pinfunction "14_14") (pintype "passive"))
      (node (ref "U1") (pin "141") (pinfunction "IO_141") (pintype "bidirectional"))
    )
    (net (code "116") (name "/PORT142") (class "Default")
      (node (ref "P5") (pin "31") (pinfunction "31_31") (pintype "passive"))
      (node (ref "U1") (pin "142") (pinfunction "IO_142") (pintype "bidirectional"))
    )
    (net (code "117") (name "/PORT143") (class "Default")
      (node (ref "P5") (pin "15") (pinfunction "15_15") (pintype "passive"))
      (node (ref "U1") (pin "143") (pinfunction "IO_143") (pintype "bidirectional"))
    )
    (net (code "118") (name "/PORT144") (class "Default")
      (node (ref "P5") (pin "32") (pinfunction "32_32") (pintype "passive"))
      (node (ref "U1") (pin "144") (pinfunction "IO_144") (pintype "bidirectional"))
    )
    (net (code "119") (name "/RESET#") (class "Default")
      (node (ref "C16") (pin "1") (pinfunction "1_1") (pintype "passive"))
      (node (ref "R6") (pin "1") (pinfunction "1_1") (pintype "passive"))
      (node (ref "S1") (pin "2") (pinfunction "2_2") (pintype "passive"))
      (node (ref "U4") (pin "49") (pinfunction "~{RESET}_49") (pintype "input"))
    )
    (net (code "120") (name "/SCL") (class "Default")
      (node (ref "P4") (pin "1") (pinfunction "1_1") (pintype "passive"))
      (node (ref "R13") (pin "2") (pintype "passive"))
      (node (ref "U4") (pin "22") (pinfunction "SCL_22") (pintype "output"))
      (node (ref "U5") (pin "6") (pinfunction "scl_6") (pintype "passive"))
    )
    (net (code "121") (name "/SDA") (class "Default")
      (node (ref "P4") (pin "2") (pinfunction "2_2") (pintype "passive"))
      (node (ref "P4") (pin "4") (pinfunction "4_4") (pintype "passive"))
      (node (ref "R14") (pin "2") (pintype "passive"))
      (node (ref "U4") (pin "23") (pinfunction "SDA_23") (pintype "output"))
    )
    (net (code "122") (name "/SDA1") (class "Default")
      (node (ref "P4") (pin "3") (pinfunction "3_3") (pintype "passive"))
      (node (ref "U5") (pin "5") (pinfunction "sda_5") (pintype "passive"))
    )
    (net (code "123") (name "/SLRD") (class "Default")
      (node (ref "U1") (pin "38") (pinfunction "IO_38") (pintype "bidirectional"))
      (node (ref "U4") (pin "8") (pinfunction "RDY0/SLRD_8") (pintype "input"))
    )
    (net (code "124") (name "/SLWR") (class "Default")
      (node (ref "U1") (pin "37") (pinfunction "IO_37") (pintype "bidirectional"))
      (node (ref "U4") (pin "9") (pinfunction "RDY1/SLWR_9") (pintype "input"))
    )
    (net (code "125") (name "/USB+") (class "Default")
      (node (ref "U4") (pin "15") (pinfunction "DPLUS_15") (pintype "bidirectional"))
      (node (ref "USB1") (pin "3") (pinfunction "3_3") (pintype "passive"))
    )
    (net (code "126") (name "/USB-") (class "Default")
      (node (ref "U4") (pin "16") (pinfunction "DMINUS_16") (pintype "bidirectional"))
      (node (ref "USB1") (pin "2") (pinfunction "2_2") (pintype "passive"))
    )
    (net (code "127") (name "/USB5V") (class "Default")
      (node (ref "C12") (pin "1") (pinfunction "1_1") (pintype "passive"))
      (node (ref "C14") (pin "1") (pinfunction "1_1") (pintype "passive"))
      (node (ref "P1") (pin "1") (pinfunction "VCC_1") (pintype "passive"))
      (node (ref "R7") (pin "2") (pintype "passive"))
      (node (ref "U3") (pin "3") (pinfunction "IN_3") (pintype "power_in"))
      (node (ref "USB1") (pin "1") (pinfunction "1_1") (pintype "passive"))
    )
    (net (code "128") (name "/WAKEUP") (class "Default")
      (node (ref "C15") (pin "1") (pinfunction "1_1") (pintype "passive"))
      (node (ref "R5") (pin "1") (pinfunction "1_1") (pintype "passive"))
      (node (ref "U4") (pin "51") (pinfunction "WAKEUP_51") (pintype "input"))
    )
    (net (code "129") (name "AUSBGND") (class "Default")
      (node (ref "C22") (pin "2") (pinfunction "2_2") (pintype "passive"))
      (node (ref "C30") (pin "2") (pinfunction "2_2") (pintype "passive"))
      (node (ref "Ind2") (pin "2") (pinfunction "2_2") (pintype "passive"))
      (node (ref "U4") (pin "13") (pinfunction "AGND_13") (pintype "power_in"))
      (node (ref "U4") (pin "17") (pinfunction "AGND_17") (pintype "power_in"))
    )
    (net (code "130") (name "AVCC3.3") (class "Default")
      (node (ref "C22") (pin "1") (pinfunction "1_1") (pintype "passive"))
      (node (ref "C30") (pin "1") (pinfunction "1_1") (pintype "passive"))
      (node (ref "Ind1") (pin "2") (pinfunction "2_2") (pintype "passive"))
      (node (ref "U4") (pin "10") (pinfunction "AVCC_10") (pintype "power_in"))
      (node (ref "U4") (pin "14") (pinfunction "AVCC_14") (pintype "power_in"))
    )
    (net (code "131") (name "DGND") (class "Default")
      (node (ref "C1") (pin "1") (pinfunction "1_1") (pintype "passive"))
      (node (ref "C10") (pin "1") (pinfunction "1_1") (pintype "passive"))
      (node (ref "C11") (pin "2") (pinfunction "2_2") (pintype "passive"))
      (node (ref "C12") (pin "2") (pinfunction "2_2") (pintype "passive"))
      (node (ref "C13") (pin "2") (pinfunction "2_2") (pintype "passive"))
      (node (ref "C14") (pin "2") (pinfunction "2_2") (pintype "passive"))
      (node (ref "C15") (pin "2") (pinfunction "2_2") (pintype "passive"))
      (node (ref "C16") (pin "2") (pinfunction "2_2") (pintype "passive"))
      (node (ref "C17") (pin "2") (pinfunction "2_2") (pintype "passive"))
      (node (ref "C18") (pin "2") (pinfunction "2_2") (pintype "passive"))
      (node (ref "C19") (pin "2") (pinfunction "2_2") (pintype "passive"))
      (node (ref "C2") (pin "1") (pinfunction "1_1") (pintype "passive"))
      (node (ref "C20") (pin "2") (pinfunction "2_2") (pintype "passive"))
      (node (ref "C23") (pin "1") (pinfunction "1_1") (pintype "passive"))
      (node (ref "C24") (pin "1") (pinfunction "1_1") (pintype "passive"))
      (node (ref "C25") (pin "1") (pinfunction "1_1") (pintype "passive"))
      (node (ref "C26") (pin "1") (pinfunction "1_1") (pintype "passive"))
      (node (ref "C27") (pin "1") (pinfunction "1_1") (pintype "passive"))
      (node (ref "C28") (pin "1") (pinfunction "1_1") (pintype "passive"))
      (node (ref "C29") (pin "1") (pinfunction "1_1") (pintype "passive"))
      (node (ref "C3") (pin "1") (pinfunction "1_1") (pintype "passive"))
      (node (ref "C4") (pin "1") (pinfunction "1_1") (pintype "passive"))
      (node (ref "C5") (pin "1") (pinfunction "1_1") (pintype "passive"))
      (node (ref "C6") (pin "1") (pinfunction "1_1") (pintype "passive"))
      (node (ref "C7") (pin "1") (pinfunction "1_1") (pintype "passive"))
      (node (ref "C8") (pin "1") (pinfunction "1_1") (pintype "passive"))
      (node (ref "C9") (pin "1") (pinfunction "1_1") (pintype "passive"))
      (node (ref "D5") (pin "1") (pinfunction "K_1") (pintype "passive"))
      (node (ref "Ind2") (pin "1") (pinfunction "1_1") (pintype "passive"))
      (node (ref "P1") (pin "2") (pinfunction "GND_2") (pintype "passive"))
      (node (ref "P1") (pin "3") (pinfunction "GND_3") (pintype "passive"))
      (node (ref "P6") (pin "10") (pinfunction "10_10") (pintype "passive"))
      (node (ref "P6") (pin "2") (pinfunction "2_2") (pintype "passive"))
      (node (ref "R11") (pin "2") (pinfunction "2_2") (pintype "passive"))
      (node (ref "R9") (pin "2") (pinfunction "2_2") (pintype "passive"))
      (node (ref "S1") (pin "1") (pinfunction "1_1") (pintype "passive"))
      (node (ref "S2") (pin "2") (pinfunction "2_2") (pintype "passive"))
      (node (ref "S3") (pin "2") (pinfunction "2_2") (pintype "passive"))
      (node (ref "U1") (pin "10") (pinfunction "GNDIO_10") (pintype "power_in"))
      (node (ref "U1") (pin "115") (pinfunction "GNDIO_115") (pintype "power_in"))
      (node (ref "U1") (pin "128") (pinfunction "GNDINT_128") (pintype "power_in"))
      (node (ref "U1") (pin "135") (pinfunction "GNDIO_135") (pintype "power_in"))
      (node (ref "U1") (pin "17") (pinfunction "GNDINT_17") (pintype "power_in"))
      (node (ref "U1") (pin "26") (pinfunction "GNDIO_26") (pintype "power_in"))
      (node (ref "U1") (pin "47") (pinfunction "GNDIO_47") (pintype "power_in"))
      (node (ref "U1") (pin "54") (pinfunction "GNDINT_54") (pintype "power_in"))
      (node (ref "U1") (pin "65") (pinfunction "GNDIO_65") (pintype "power_in"))
      (node (ref "U1") (pin "83") (pinfunction "GNDIO_83") (pintype "power_in"))
      (node (ref "U1") (pin "92") (pinfunction "GNDINT_92") (pintype "power_in"))
      (node (ref "U1") (pin "99") (pinfunction "GNDIO_99") (pintype "power_in"))
      (node (ref "U3") (pin "1") (pinfunction "ADJ_1") (pintype "input"))
      (node (ref "U4") (pin "19") (pinfunction "GND_19") (pintype "power_in"))
      (node (ref "U4") (pin "33") (pinfunction "GND_33") (pintype "power_in"))
      (node (ref "U4") (pin "35") (pinfunction "GND_35") (pintype "power_in"))
      (node (ref "U4") (pin "4") (pinfunction "GND_4") (pintype "power_in"))
      (node (ref "U4") (pin "48") (pinfunction "GND_48") (pintype "power_in"))
      (node (ref "U4") (pin "7") (pinfunction "GND_7") (pintype "power_in"))
      (node (ref "U5") (pin "2") (pinfunction "A1_2") (pintype "passive"))
      (node (ref "U5") (pin "3") (pinfunction "A2_3") (pintype "passive"))
      (node (ref "U5") (pin "4") (pinfunction "gnd_4") (pintype "passive"))
      (node (ref "U6") (pin "2") (pinfunction "GND_2") (pintype "passive"))
      (node (ref "USB1") (pin "0") (pinfunction "GND_0") (pintype "passive"))
      (node (ref "USB1") (pin "4") (pinfunction "4_4") (pintype "passive"))
    )
    (net (code "132") (name "GND") (class "Default")
      (node (ref "P2") (pin "17") (pinfunction "17_17") (pintype "passive"))
      (node (ref "P2") (pin "19") (pinfunction "19_19") (pintype "passive"))
      (node (ref "P2") (pin "2") (pinfunction "2_2") (pintype "passive"))
      (node (ref "P2") (pin "26") (pinfunction "26_26") (pintype "passive"))
      (node (ref "P2") (pin "34") (pinfunction "34_34") (pintype "passive"))
      (node (ref "P2") (pin "9") (pinfunction "9_9") (pintype "passive"))
      (node (ref "P3") (pin "16") (pinfunction "16_16") (pintype "passive"))
      (node (ref "P3") (pin "33") (pinfunction "33_33") (pintype "passive"))
      (node (ref "P5") (pin "1") (pinfunction "1_1") (pintype "passive"))
      (node (ref "P5") (pin "16") (pinfunction "16_16") (pintype "passive"))
      (node (ref "P5") (pin "18") (pinfunction "18_18") (pintype "passive"))
      (node (ref "P5") (pin "33") (pinfunction "33_33") (pintype "passive"))
      (node (ref "U2") (pin "12") (pinfunction "GND_12") (pintype "power_in"))
      (node (ref "U2") (pin "34") (pinfunction "GND_34") (pintype "power_in"))
      (node (ref "U2") (pin "39") (pinfunction "LB#_39") (pintype "input"))
      (node (ref "U2") (pin "40") (pinfunction "UB#_40") (pintype "input"))
    )
    (net (code "133") (name "Net-(D1-K)") (class "Default")
      (node (ref "D1") (pin "1") (pinfunction "K_1") (pintype "passive"))
      (node (ref "R1") (pin "1") (pinfunction "1_1") (pintype "passive"))
    )
    (net (code "134") (name "Net-(D2-K)") (class "Default")
      (node (ref "D2") (pin "1") (pinfunction "K_1") (pintype "passive"))
      (node (ref "R2") (pin "1") (pinfunction "1_1") (pintype "passive"))
    )
    (net (code "135") (name "Net-(D5-A)") (class "Default")
      (node (ref "D5") (pin "2") (pinfunction "A_2") (pintype "passive"))
      (node (ref "R7") (pin "1") (pintype "passive"))
    )
    (net (code "136") (name "Net-(U4-RESERVED)") (class "Default")
      (node (ref "R11") (pin "1") (pinfunction "1_1") (pintype "passive"))
      (node (ref "U4") (pin "21") (pinfunction "RESERVED_21") (pintype "input"))
    )
    (net (code "137") (name "Net-(U4-XTALIN)") (class "Default")
      (node (ref "C17") (pin "1") (pinfunction "1_1") (pintype "passive"))
      (node (ref "U4") (pin "12") (pinfunction "XTALIN_12") (pintype "input"))
      (node (ref "Y1") (pin "1") (pinfunction "OSC1_1") (pintype "passive"))
    )
    (net (code "138") (name "Net-(U4-XTALOUT)") (class "Default")
      (node (ref "C18") (pin "1") (pinfunction "1_1") (pintype "passive"))
      (node (ref "U4") (pin "11") (pinfunction "XTALOUT_11") (pintype "output"))
      (node (ref "Y1") (pin "2") (pinfunction "OSC2_2") (pintype "passive"))
    )
    (net (code "139") (name "Net-(U5-A0)") (class "Default")
      (node (ref "R8") (pin "1") (pinfunction "1_1") (pintype "passive"))
      (node (ref "R9") (pin "1") (pinfunction "1_1") (pintype "passive"))
      (node (ref "U5") (pin "1") (pinfunction "A0_1") (pintype "passive"))
    )
    (net (code "140") (name "VCC3.3") (class "Default")
      (node (ref "C1") (pin "2") (pinfunction "2_2") (pintype "passive"))
      (node (ref "C10") (pin "2") (pinfunction "2_2") (pintype "passive"))
      (node (ref "C11") (pin "1") (pinfunction "1_1") (pintype "passive"))
      (node (ref "C13") (pin "1") (pinfunction "1_1") (pintype "passive"))
      (node (ref "C2") (pin "2") (pinfunction "2_2") (pintype "passive"))
      (node (ref "C23") (pin "2") (pinfunction "2_2") (pintype "passive"))
      (node (ref "C24") (pin "2") (pinfunction "2_2") (pintype "passive"))
      (node (ref "C25") (pin "2") (pinfunction "2_2") (pintype "passive"))
      (node (ref "C26") (pin "2") (pinfunction "2_2") (pintype "passive"))
      (node (ref "C27") (pin "2") (pinfunction "2_2") (pintype "passive"))
      (node (ref "C28") (pin "2") (pinfunction "2_2") (pintype "passive"))
      (node (ref "C29") (pin "2") (pinfunction "2_2") (pintype "passive"))
      (node (ref "C3") (pin "2") (pinfunction "2_2") (pintype "passive"))
      (node (ref "C4") (pin "2") (pinfunction "2_2") (pintype "passive"))
      (node (ref "C5") (pin "2") (pinfunction "2_2") (pintype "passive"))
      (node (ref "C6") (pin "2") (pinfunction "2_2") (pintype "passive"))
      (node (ref "C7") (pin "2") (pinfunction "2_2") (pintype "passive"))
      (node (ref "C8") (pin "2") (pinfunction "2_2") (pintype "passive"))
      (node (ref "C9") (pin "2") (pinfunction "2_2") (pintype "passive"))
      (node (ref "D1") (pin "2") (pinfunction "A_2") (pintype "passive"))
      (node (ref "D2") (pin "2") (pinfunction "A_2") (pintype "passive"))
      (node (ref "Ind1") (pin "1") (pinfunction "1_1") (pintype "passive"))
      (node (ref "P2") (pin "1") (pinfunction "1_1") (pintype "passive"))
      (node (ref "P2") (pin "18") (pinfunction "18_18") (pintype "passive"))
      (node (ref "P3") (pin "17") (pinfunction "17_17") (pintype "passive"))
      (node (ref "P3") (pin "34") (pinfunction "34_34") (pintype "passive"))
      (node (ref "P5") (pin "17") (pinfunction "17_17") (pintype "passive"))
      (node (ref "P5") (pin "34") (pinfunction "34_34") (pintype "passive"))
      (node (ref "P6") (pin "4") (pinfunction "4_4") (pintype "passive"))
      (node (ref "R10") (pin "2") (pinfunction "2_2") (pintype "passive"))
      (node (ref "R12") (pin "2") (pinfunction "2_2") (pintype "passive"))
      (node (ref "R13") (pin "1") (pintype "passive"))
      (node (ref "R14") (pin "1") (pintype "passive"))
      (node (ref "R16") (pin "2") (pinfunction "2_2") (pintype "passive"))
      (node (ref "R17") (pin "2") (pinfunction "2_2") (pintype "passive"))
      (node (ref "R18") (pin "2") (pinfunction "2_2") (pintype "passive"))
      (node (ref "R5") (pin "2") (pinfunction "2_2") (pintype "passive"))
      (node (ref "R6") (pin "2") (pinfunction "2_2") (pintype "passive"))
      (node (ref "R8") (pin "2") (pinfunction "2_2") (pintype "passive"))
      (node (ref "U1") (pin "100") (pinfunction "VCCIO3_100") (pintype "power_in"))
      (node (ref "U1") (pin "116") (pinfunction "VCCIO2_116") (pintype "power_in"))
      (node (ref "U1") (pin "126") (pinfunction "VCCINT_126") (pintype "power_in"))
      (node (ref "U1") (pin "136") (pinfunction "VCCIO2_136") (pintype "power_in"))
      (node (ref "U1") (pin "19") (pinfunction "VCCINT_19") (pintype "power_in"))
      (node (ref "U1") (pin "25") (pinfunction "VCCIO1_25") (pintype "power_in"))
      (node (ref "U1") (pin "46") (pinfunction "VCCIO4_46") (pintype "power_in"))
      (node (ref "U1") (pin "56") (pinfunction "VCCINT_56") (pintype "power_in"))
      (node (ref "U1") (pin "64") (pinfunction "VCCIO4_64") (pintype "power_in"))
      (node (ref "U1") (pin "82") (pinfunction "VCCIO3_82") (pintype "power_in"))
      (node (ref "U1") (pin "9") (pinfunction "VCCIO1_9") (pintype "power_in"))
      (node (ref "U1") (pin "90") (pinfunction "VCCINT_90") (pintype "power_in"))
      (node (ref "U2") (pin "11") (pinfunction "VCC_11") (pintype "power_in"))
      (node (ref "U2") (pin "33") (pinfunction "VCC_33") (pintype "power_in"))
      (node (ref "U3") (pin "2") (pinfunction "OUT_2") (pintype "power_in"))
      (node (ref "U4") (pin "18") (pinfunction "VCC_18") (pintype "power_in"))
      (node (ref "U4") (pin "24") (pinfunction "VCC_24") (pintype "power_in"))
      (node (ref "U4") (pin "34") (pinfunction "VCC_34") (pintype "power_in"))
      (node (ref "U4") (pin "39") (pinfunction "VCC_39") (pintype "power_in"))
      (node (ref "U4") (pin "50") (pinfunction "VCC_50") (pintype "power_in"))
      (node (ref "U4") (pin "6") (pinfunction "VCC_6") (pintype "power_in"))
      (node (ref "U5") (pin "8") (pinfunction "vcc_8") (pintype "passive"))
      (node (ref "U6") (pin "4") (pinfunction "VCC_4") (pintype "passive"))
    )
    (net (code "141") (name "unconnected-(P6-Pad6)") (class "Default")
      (node (ref "P6") (pin "6") (pinfunction "6_6") (pintype "passive"))
    )
    (net (code "142") (name "unconnected-(P6-Pad7)") (class "Default")
      (node (ref "P6") (pin "7") (pinfunction "7_7") (pintype "passive+no_connect"))
    )
    (net (code "143") (name "unconnected-(P6-Pad8)") (class "Default")
      (node (ref "P6") (pin "8") (pinfunction "8_8") (pintype "passive+no_connect"))
    )
    (net (code "144") (name "unconnected-(U5-nc-Pad7)") (class "Default")
      (node (ref "U5") (pin "7") (pinfunction "nc_7") (pintype "passive+no_connect"))
    )
    (net (code "145") (name "unconnected-(U6-NC-Pad1)") (class "Default")
      (node (ref "U6") (pin "1") (pinfunction "NC_1") (pintype "passive+no_connect"))
    )
  )
)
